# 1_2V_POWER.net
KiCad netlist of a schematic drawn in Altium Designer
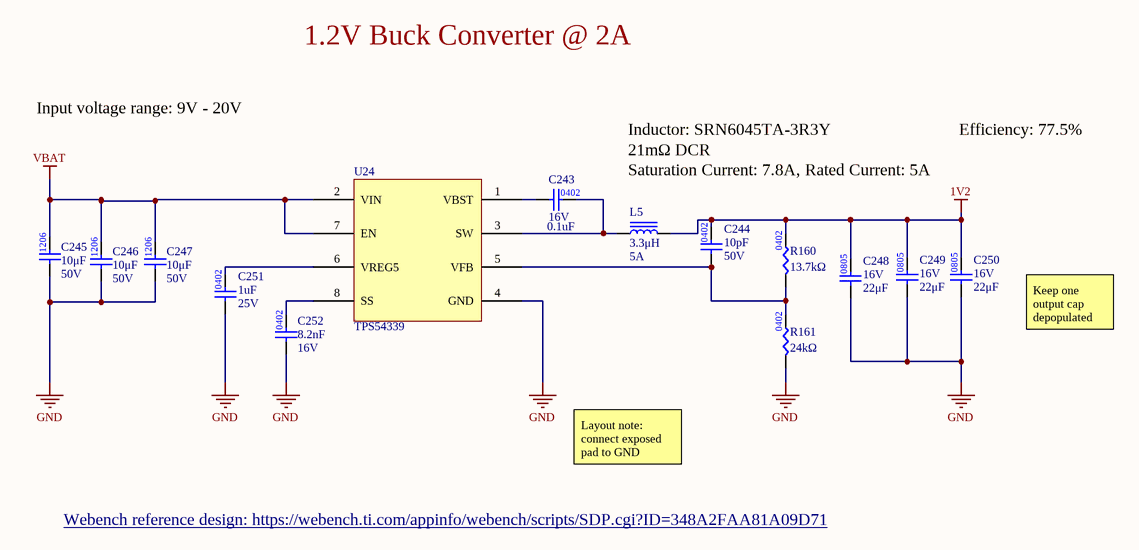
[diagram p0: 1.2V POWER.SchDoc]

(export (version "E")
  (design (tool "Eeschema 10.0.6"))
  (components
    (comp (ref "C243")
      (value "CAP_0.1uF_16V_X7R_0402")
      (footprint "CAP0402")
      (description "Ceramic Capacitor, Ceramic")
      (fields
        (field (name "MANUFACTURER") "Taiyo Yuden")
        (field (name "MANUFACTURER PART NUMBER") "LMK212AC6106MD-T")
        (field (name "RATED DC VOLTAGE (URDC)") "16V")
        (field (name "CAPACITANCE") "0.1uF")
      )
      (libsource (lib "UWRT_Schematic_Library_2020") (part "CAP_0.1uF_16V_X7R_0402"))
    )
    (comp (ref "C244")
      (value "CAP_10pF_50V_0402")
      (footprint "CAP0402")
      (fields (field (name "CAPACITANCE") "10pF") (field (name "VOLTAGE") "50V"))
      (libsource (lib "UWRT_Schematic_Library_2020") (part "CAP_10pF_50V_0402"))
    )
    (comp (ref "C245")
      (value "10μF")
      (footprint "CAP1210")
      (description "CAP CER 10UF 50V X7R 1210")
      (fields (field (name "VOLTAGE RATING") "50V") (field (name "Comment") "CAP_10uF_50V_1210"))
      (libsource (lib "UWRT_Schematic_Library_2020") (part "CAP_10uF_50V_1210"))
    )
    (comp (ref "C246")
      (value "10μF")
      (footprint "CAP1210")
      (description "CAP CER 10UF 50V X7R 1210")
      (fields (field (name "VOLTAGE RATING") "50V") (field (name "Comment") "CAP_10uF_50V_1210"))
      (libsource (lib "UWRT_Schematic_Library_2020") (part "CAP_10uF_50V_1210"))
    )
    (comp (ref "C247")
      (value "10μF")
      (footprint "CAP1210")
      (description "CAP CER 10UF 50V X7R 1210")
      (fields (field (name "VOLTAGE RATING") "50V") (field (name "Comment") "CAP_10uF_50V_1210"))
      (libsource (lib "UWRT_Schematic_Library_2020") (part "CAP_10uF_50V_1210"))
    )
    (comp (ref "C248")
      (value "22μF")
      (footprint "CAP2012")
      (description "CAP CER 22UF 16V X5R 0805")
      (fields (field (name "VOLTAGE RATING") "16V") (field (name "Comment") "CAP_22uF_16V_0805"))
      (libsource (lib "UWRT_Schematic_Library_2020") (part "CAP_22uF_16V_0805"))
    )
    (comp (ref "C249")
      (value "22μF")
      (footprint "CAP2012")
      (description "CAP CER 22UF 16V X5R 0805")
      (fields (field (name "VOLTAGE RATING") "16V") (field (name "Comment") "CAP_22uF_16V_0805"))
      (libsource (lib "UWRT_Schematic_Library_2020") (part "CAP_22uF_16V_0805"))
    )
    (comp (ref "C250")
      (value "22μF")
      (footprint "CAP2012")
      (description "CAP CER 22UF 16V X5R 0805")
      (fields (field (name "VOLTAGE RATING") "16V") (field (name "Comment") "CAP_22uF_16V_0805"))
      (libsource (lib "UWRT_Schematic_Library_2020") (part "CAP_22uF_16V_0805"))
    )
    (comp (ref "C251")
      (value "CAP_1uF_25V_0402")
      (footprint "CAP0402")
      (description "±10% 25V Ceramic Capacitor X5R 0402 (1005 Metric)")
      (fields (field (name "CAPACITANCE") "1uF") (field (name "VOLTAGE") "25V"))
      (libsource (lib "UWRT_Schematic_Library_2020") (part "CAP_1uF_25V_0402"))
    )
    (comp (ref "C252")
      (value "CAP_8.2nF_16V_0402")
      (footprint "CAP0402")
      (description "8200 pF ±10% 16V Ceramic Capacitor X7R 0402 (1005 Metric)")
      (fields (field (name "CAPACITANCE") "8.2nF") (field (name "VOLTAGE") "16V"))
      (libsource (lib "UWRT_Schematic_Library_2020") (part "CAP_8.2nF_16V_0402"))
    )
    (comp (ref "L5")
      (value "IND_3.3uH_5A")
      (footprint "IND_SRN6045TA-3R3Y")
      (description "FIXED IND 3.3UH 5A 21 MOHM SMD")
      (fields (field (name "CURRENT RATING") "5A") (field (name "INDUCTANCE") "3.3μH"))
      (libsource (lib "UWRT_Schematic_Library_2020") (part "IND_3.3uH_5A"))
    )
    (comp (ref "R160")
      (value "13.7kΩ")
      (footprint "RES0402")
      (description "RES SMD 13.7K OHM 1% 1/16W 0402")
      (fields (field (name "POWER") "0.063W, 1/16W") (field (name "TOLERANCE") "1%"))
      (libsource (lib "UWRT_Schematic_Library_2020") (part "RES_13.7kΩ_0402_1%"))
    )
    (comp (ref "R161")
      (value "24kΩ")
      (footprint "RES0402")
      (description "RES SMD 24K OHM 1% 1/16W 0402")
      (fields (field (name "POWER") "0.063W, 1/16W") (field (name "TOLERANCE") "1%"))
      (libsource (lib "UWRT_Schematic_Library_2020") (part "RES_24kΩ_0402_1%"))
    )
    (comp (ref "U24")
      (value "TPS54339")
      (footprint "VREG_LM5017MR/NOPB")
      (description "IC REG BUCK ADJUSTABLE 3A 8SOPWR")
      (libsource (lib "UWRT_Schematic_Library_2020") (part "TPS54339"))
    )
  )
  (nets
    (net (code "1") (name "1V2") (class "Default")
      (node (ref "C244") (pin "2") (pinfunction "2_2") (pintype "passive"))
      (node (ref "C248") (pin "2") (pinfunction "2_2") (pintype "passive"))
      (node (ref "C249") (pin "2") (pinfunction "2_2") (pintype "passive"))
      (node (ref "C250") (pin "2") (pinfunction "2_2") (pintype "passive"))
      (node (ref "L5") (pin "2") (pinfunction "2_2") (pintype "passive"))
      (node (ref "R160") (pin "2") (pinfunction "2_2") (pintype "passive"))
    )
    (net (code "2") (name "GND") (class "Default")
      (node (ref "C245") (pin "1") (pinfunction "1_1") (pintype "passive"))
      (node (ref "C246") (pin "1") (pinfunction "1_1") (pintype "passive"))
      (node (ref "C247") (pin "1") (pinfunction "1_1") (pintype "passive"))
      (node (ref "C248") (pin "1") (pinfunction "1_1") (pintype "passive"))
      (node (ref "C249") (pin "1") (pinfunction "1_1") (pintype "passive"))
      (node (ref "C250") (pin "1") (pinfunction "1_1") (pintype "passive"))
      (node (ref "C251") (pin "1") (pinfunction "1_1") (pintype "passive"))
      (node (ref "C252") (pin "1") (pinfunction "1_1") (pintype "passive"))
      (node (ref "R161") (pin "1") (pinfunction "1_1") (pintype "passive"))
      (node (ref "U24") (pin "4") (pinfunction "GND_4") (pintype "passive"))
    )
    (net (code "3") (name "Net-(U24-SS)") (class "Default")
      (node (ref "C252") (pin "2") (pinfunction "2_2") (pintype "passive"))
      (node (ref "U24") (pin "8") (pinfunction "SS_8") (pintype "passive"))
    )
    (net (code "4") (name "Net-(U24-SW)") (class "Default")
      (node (ref "C243") (pin "2") (pinfunction "2_2") (pintype "passive"))
      (node (ref "L5") (pin "1") (pinfunction "1_1") (pintype "passive"))
      (node (ref "U24") (pin "3") (pinfunction "SW_3") (pintype "passive"))
    )
    (net (code "5") (name "Net-(U24-VBST)") (class "Default")
      (node (ref "C243") (pin "1") (pinfunction "1_1") (pintype "passive"))
      (node (ref "U24") (pin "1") (pinfunction "VBST_1") (pintype "passive"))
    )
    (net (code "6") (name "Net-(U24-VFB)") (class "Default")
      (node (ref "C244") (pin "1") (pinfunction "1_1") (pintype "passive"))
      (node (ref "R160") (pin "1") (pinfunction "1_1") (pintype "passive"))
      (node (ref "R161") (pin "2") (pinfunction "2_2") (pintype "passive"))
      (node (ref "U24") (pin "5") (pinfunction "VFB_5") (pintype "passive"))
    )
    (net (code "7") (name "Net-(U24-VREG5)") (class "Default")
      (node (ref "C251") (pin "2") (pinfunction "2_2") (pintype "passive"))
      (node (ref "U24") (pin "6") (pinfunction "VREG5_6") (pintype "passive"))
    )
    (net (code "8") (name "VBAT") (class "Default")
      (node (ref "C245") (pin "2") (pinfunction "2_2") (pintype "passive"))
      (node (ref "C246") (pin "2") (pinfunction "2_2") (pintype "passive"))
      (node (ref "C247") (pin "2") (pinfunction "2_2") (pintype "passive"))
      (node (ref "U24") (pin "2") (pinfunction "VIN_2") (pintype "passive"))
      (node (ref "U24") (pin "7") (pinfunction "EN_7") (pintype "passive"))
    )
  )
)
